# Pixel1_0_0.net
KiCad netlist of a schematic drawn in Altium Designer
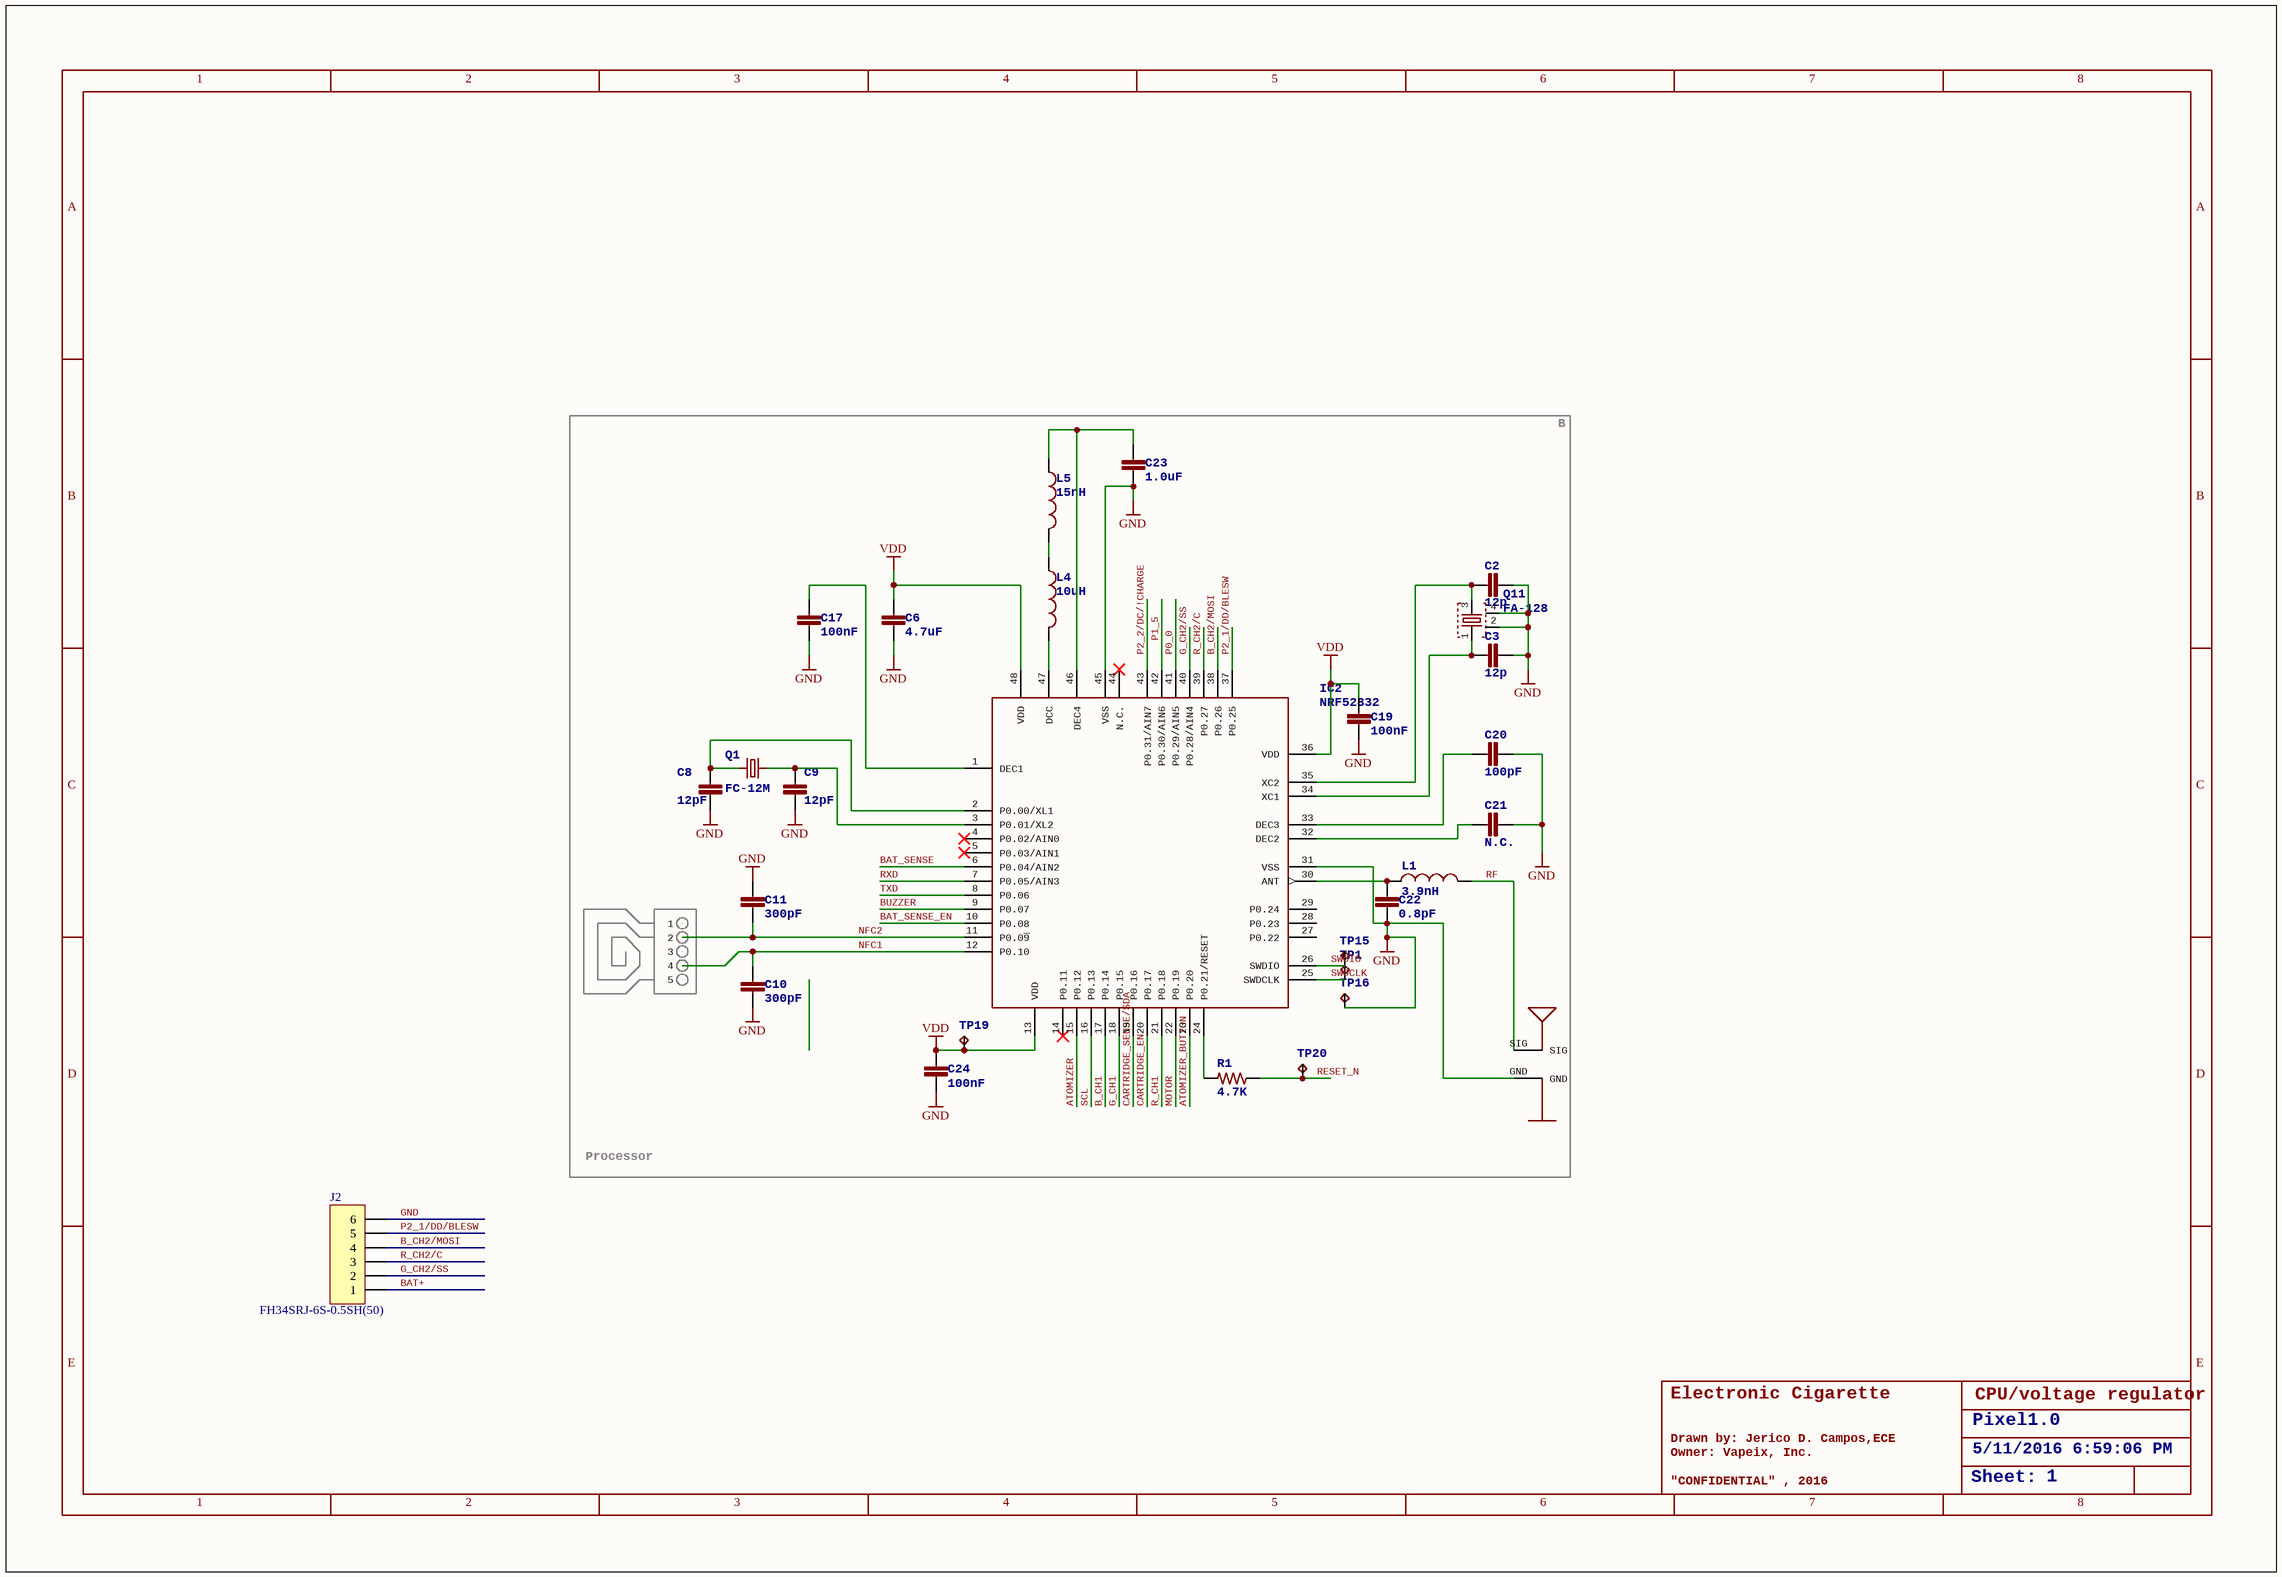
[diagram p0: Pixel1.0_0.SchDoc]

(export (version "E")
  (design (tool "Eeschema 10.0.6"))
  (components
    (comp (ref "ANT") (value "U.FL") (footprint "U.FL") (libsource (lib "Pixel1.0") (part "U.FL")))
    (comp (ref "C2")
      (value "12p")
      (footprint "C0201")
      (description "CAPACITOR, European symbol")
      (libsource (lib "") (part "C-EUC0201_1"))
    )
    (comp (ref "C3")
      (value "12p")
      (footprint "C0201")
      (description "CAPACITOR, European symbol")
      (libsource (lib "rcl") (part "C-EUC0201"))
    )
    (comp (ref "C6")
      (value "4.7uF")
      (footprint "C0201")
      (description "CAPACITOR, European symbol")
      (libsource (lib "") (part "C-EUC0201_2"))
    )
    (comp (ref "C8")
      (value "12pF")
      (footprint "C0201")
      (description "CAPACITOR, European symbol")
      (libsource (lib "") (part "C-EUC0201_2"))
    )
    (comp (ref "C9")
      (value "12pF")
      (footprint "C0201")
      (description "CAPACITOR, European symbol")
      (libsource (lib "") (part "C-EUC0201_2"))
    )
    (comp (ref "C10")
      (value "300pF")
      (footprint "C0201")
      (description "CAPACITOR, European symbol")
      (libsource (lib "") (part "C-EUC0201_2"))
    )
    (comp (ref "C11")
      (value "300pF")
      (footprint "C0201")
      (description "CAPACITOR, European symbol")
      (libsource (lib "") (part "C-EUC0201_3"))
    )
    (comp (ref "C17")
      (value "100nF")
      (footprint "C0201")
      (description "CAPACITOR, European symbol")
      (libsource (lib "") (part "C-EUC0201_2"))
    )
    (comp (ref "C19")
      (value "100nF")
      (footprint "C0201")
      (description "CAPACITOR, European symbol")
      (libsource (lib "") (part "C-EUC0201_2"))
    )
    (comp (ref "C20")
      (value "100pF")
      (footprint "C0201")
      (description "CAPACITOR, European symbol")
      (libsource (lib "rcl") (part "C-EUC0201"))
    )
    (comp (ref "C21")
      (value "N.C.")
      (footprint "C0201")
      (description "CAPACITOR, European symbol")
      (libsource (lib "rcl") (part "C-EUC0201"))
    )
    (comp (ref "C22")
      (value "0.8pF")
      (footprint "C0201")
      (description "CAPACITOR, European symbol")
      (libsource (lib "") (part "C-EUC0201_2"))
    )
    (comp (ref "C23")
      (value "1.0uF")
      (footprint "C0201")
      (description "CAPACITOR, European symbol")
      (libsource (lib "") (part "C-EUC0201_2"))
    )
    (comp (ref "C24")
      (value "100nF")
      (footprint "C0201")
      (description "CAPACITOR, European symbol")
      (libsource (lib "") (part "C-EUC0201_2"))
    )
    (comp (ref "IC2") (value "NRF52832") (footprint "QFN-48") (libsource (lib "FTDI") (part "NRF52832")))
    (comp (ref "J2")
      (value "FH34SRJ-6S-0.5SH(50)")
      (footprint "59453061110ECHLF")
      (description "WR-FPC 0.50mm SMT ZIF Horizontal Bottom Contact")
      (fields
        (field (name "MANUFACTURER") "Würth Elektronik eiSos GmbH")
        (field (name "PARTNO") "68710614522")
        (field (name "CREATED BY") "Karrer Zheng")
      )
      (libsource (lib "Components") (part "WE-ZIF Connector WR-FPC 68710614522"))
    )
    (comp (ref "L1") (value "3.9nH") (footprint "JE0402") (libsource (lib "vapeix") (part "LBEAD")))
    (comp (ref "L4") (value "10uH") (footprint "C0603") (libsource (lib "vapeix") (part "LBEAD")))
    (comp (ref "L5") (value "15nH") (footprint "JE0402") (libsource (lib "vapeix") (part "LBEAD")))
    (comp (ref "Q1")
      (value "FC-12M")
      (footprint "FC-12M")
      (description "kHz RANGE CRYSTAL UNIT   LOW PROFILE SMDSource: Epson Toyocom FC-12M.pdf")
      (libsource (lib "crystal") (part "FC-12M"))
    )
    (comp (ref "Q11")
      (value "FA-128")
      (footprint "FA-128")
      (description "MHz RANGE CRYSTAL UNIT    Source: Epson Toyocom")
      (libsource (lib "crystal") (part "FA-128"))
    )
    (comp (ref "R1")
      (value "4.7K")
      (footprint "R0201")
      (description "RESISTOR, American symbol")
      (libsource (lib "rcl") (part "R-US_R0201"))
    )
    (comp (ref "TP1")
      (value "TPTP06R")
      (footprint "TP06R")
      (description "Test pad")
      (libsource (lib "testpad") (part "TPTP06R"))
    )
    (comp (ref "TP15")
      (value "TPTP06R")
      (footprint "TP06R")
      (description "Test pad")
      (libsource (lib "testpad") (part "TPTP06R"))
    )
    (comp (ref "TP16")
      (value "TPTP06R")
      (footprint "TP06R")
      (description "Test pad")
      (libsource (lib "testpad") (part "TPTP06R"))
    )
    (comp (ref "TP19")
      (value "TPTP06R")
      (footprint "TP06R")
      (description "Test pad")
      (libsource (lib "testpad") (part "TPTP06R"))
    )
    (comp (ref "TP20")
      (value "TPTP06R")
      (footprint "TP06R")
      (description "Test pad")
      (libsource (lib "testpad") (part "TPTP06R"))
    )
    (comp (ref "U$2")
      (value "NFCCONNECTORMOLEX_5PIN")
      (footprint "NFC.CONN")
      (libsource (lib "vapeix") (part "NFCCONNECTORMOLEX_5PIN"))
    )
  )
  (nets
    (net (code "1") (name "/ATOMIZER") (class "Default")
      (node (ref "IC2") (pin "15") (pinfunction "P0.12_15") (pintype "passive"))
    )
    (net (code "2") (name "/ATOMIZER_BUTTON") (class "Default")
      (node (ref "IC2") (pin "23") (pinfunction "P0.20_23") (pintype "passive"))
    )
    (net (code "3") (name "/BAT+") (class "Default")
      (node (ref "J2") (pin "1") (pinfunction "1_1") (pintype "passive"))
    )
    (net (code "4") (name "/BAT_SENSE") (class "Default")
      (node (ref "IC2") (pin "6") (pinfunction "P0.04/AIN2_6") (pintype "passive"))
    )
    (net (code "5") (name "/BAT_SENSE_EN") (class "Default")
      (node (ref "IC2") (pin "10") (pinfunction "P0.08_10") (pintype "passive"))
    )
    (net (code "6") (name "/BUZZER") (class "Default")
      (node (ref "IC2") (pin "9") (pinfunction "P0.07_9") (pintype "passive"))
    )
    (net (code "7") (name "/B_CH1") (class "Default")
      (node (ref "IC2") (pin "17") (pinfunction "P0.14_17") (pintype "passive"))
    )
    (net (code "8") (name "/B_CH2{slash}MOSI") (class "Default")
      (node (ref "IC2") (pin "38") (pinfunction "P0.26_38") (pintype "passive"))
      (node (ref "J2") (pin "4") (pinfunction "4_4") (pintype "passive"))
    )
    (net (code "9") (name "/CARTRIDGE_EN") (class "Default")
      (node (ref "IC2") (pin "20") (pinfunction "P0.17_20") (pintype "passive"))
    )
    (net (code "10") (name "/CARTRIDGE_SENSE{slash}SDA") (class "Default")
      (node (ref "IC2") (pin "19") (pinfunction "P0.16_19") (pintype "passive"))
    )
    (net (code "11") (name "/G_CH1") (class "Default")
      (node (ref "IC2") (pin "18") (pinfunction "P0.15_18") (pintype "passive"))
    )
    (net (code "12") (name "/G_CH2{slash}SS") (class "Default")
      (node (ref "IC2") (pin "40") (pinfunction "P0.28/AIN4_40") (pintype "passive"))
      (node (ref "J2") (pin "2") (pinfunction "2_2") (pintype "passive"))
    )
    (net (code "13") (name "/MOTOR") (class "Default")
      (node (ref "IC2") (pin "22") (pinfunction "P0.19_22") (pintype "passive"))
    )
    (net (code "14") (name "/NFC1") (class "Default")
      (node (ref "C10") (pin "1") (pinfunction "1_1") (pintype "passive"))
      (node (ref "IC2") (pin "12") (pinfunction "P0.10_12") (pintype "passive"))
      (node (ref "U$2") (pin "4") (pinfunction "4_4") (pintype "passive"))
    )
    (net (code "15") (name "/NFC2") (class "Default")
      (node (ref "C11") (pin "1") (pinfunction "1_1") (pintype "passive"))
      (node (ref "IC2") (pin "11") (pinfunction "P0.0~{9}_11") (pintype "passive"))
      (node (ref "U$2") (pin "2") (pinfunction "2_2") (pintype "passive"))
    )
    (net (code "16") (name "/P0_0") (class "Default")
      (node (ref "IC2") (pin "41") (pinfunction "P0.29/AIN5_41") (pintype "passive"))
    )
    (net (code "17") (name "/P1_5") (class "Default")
      (node (ref "IC2") (pin "42") (pinfunction "P0.30/AIN6_42") (pintype "passive"))
    )
    (net (code "18") (name "/P2_1{slash}DD{slash}BLESW") (class "Default")
      (node (ref "IC2") (pin "37") (pinfunction "P0.25_37") (pintype "passive"))
      (node (ref "J2") (pin "5") (pinfunction "5_5") (pintype "passive"))
    )
    (net (code "19") (name "/P2_2{slash}DC{slash}!CHARGE") (class "Default")
      (node (ref "IC2") (pin "43") (pinfunction "P0.31/AIN7_43") (pintype "passive"))
    )
    (net (code "20") (name "/RESET_N") (class "Default")
      (node (ref "R1") (pin "1") (pinfunction "1_1") (pintype "passive"))
      (node (ref "TP20") (pin "TP") (pinfunction "TP_TP") (pintype "passive"))
    )
    (net (code "21") (name "/RF") (class "Default")
      (node (ref "ANT") (pin "SIG") (pinfunction "SIG_SIG") (pintype "passive"))
      (node (ref "L1") (pin "2") (pinfunction "2_2") (pintype "passive"))
    )
    (net (code "22") (name "/RXD") (class "Default")
      (node (ref "IC2") (pin "7") (pinfunction "P0.05/AIN3_7") (pintype "passive"))
    )
    (net (code "23") (name "/R_CH1") (class "Default")
      (node (ref "IC2") (pin "21") (pinfunction "P0.18_21") (pintype "passive"))
    )
    (net (code "24") (name "/R_CH2{slash}C") (class "Default")
      (node (ref "IC2") (pin "39") (pinfunction "P0.27_39") (pintype "passive"))
      (node (ref "J2") (pin "3") (pinfunction "3_3") (pintype "passive"))
    )
    (net (code "25") (name "/SCL") (class "Default")
      (node (ref "IC2") (pin "16") (pinfunction "P0.13_16") (pintype "passive"))
    )
    (net (code "26") (name "/SWDCLK") (class "Default")
      (node (ref "IC2") (pin "25") (pinfunction "SWDCLK_25") (pintype "open_collector"))
      (node (ref "TP1") (pin "TP") (pinfunction "TP_TP") (pintype "passive"))
    )
    (net (code "27") (name "/SWDIO") (class "Default")
      (node (ref "IC2") (pin "26") (pinfunction "SWDIO_26") (pintype "open_collector"))
      (node (ref "TP15") (pin "TP") (pinfunction "TP_TP") (pintype "passive"))
    )
    (net (code "28") (name "/TXD") (class "Default")
      (node (ref "IC2") (pin "8") (pinfunction "P0.06_8") (pintype "passive"))
    )
    (net (code "29") (name "GND") (class "Default")
      (node (ref "ANT") (pin "GND") (pinfunction "GND_GND") (pintype "passive"))
      (node (ref "C10") (pin "2") (pinfunction "2_2") (pintype "passive"))
      (node (ref "C11") (pin "2") (pinfunction "2_2") (pintype "passive"))
      (node (ref "C17") (pin "2") (pinfunction "2_2") (pintype "passive"))
      (node (ref "C19") (pin "2") (pinfunction "2_2") (pintype "passive"))
      (node (ref "C2") (pin "2") (pinfunction "2_2") (pintype "passive"))
      (node (ref "C20") (pin "1") (pinfunction "1_1") (pintype "passive"))
      (node (ref "C21") (pin "1") (pinfunction "1_1") (pintype "passive"))
      (node (ref "C22") (pin "2") (pinfunction "2_2") (pintype "passive"))
      (node (ref "C23") (pin "2") (pinfunction "2_2") (pintype "passive"))
      (node (ref "C24") (pin "2") (pinfunction "2_2") (pintype "passive"))
      (node (ref "C3") (pin "1") (pinfunction "1_1") (pintype "passive"))
      (node (ref "C6") (pin "2") (pinfunction "2_2") (pintype "passive"))
      (node (ref "C8") (pin "2") (pinfunction "2_2") (pintype "passive"))
      (node (ref "C9") (pin "2") (pinfunction "2_2") (pintype "passive"))
      (node (ref "IC2") (pin "31") (pinfunction "VSS_31") (pintype "power_in"))
      (node (ref "IC2") (pin "45") (pinfunction "VSS_45") (pintype "power_in"))
      (node (ref "J2") (pin "6") (pinfunction "6_6") (pintype "passive"))
      (node (ref "Q11") (pin "2") (pinfunction "2_2") (pintype "passive"))
      (node (ref "Q11") (pin "4") (pinfunction "4_4") (pintype "passive"))
      (node (ref "TP16") (pin "TP") (pinfunction "TP_TP") (pintype "passive"))
    )
    (net (code "30") (name "Net-(IC2-ANT)") (class "Default")
      (node (ref "C22") (pin "1") (pinfunction "1_1") (pintype "passive"))
      (node (ref "IC2") (pin "30") (pinfunction "ANT_30") (pintype "output"))
      (node (ref "L1") (pin "1") (pinfunction "1_1") (pintype "passive"))
    )
    (net (code "31") (name "Net-(IC2-DCC)") (class "Default")
      (node (ref "IC2") (pin "47") (pinfunction "DCC_47") (pintype "power_in"))
      (node (ref "L4") (pin "2") (pinfunction "2_2") (pintype "passive"))
    )
    (net (code "32") (name "Net-(IC2-DEC1)") (class "Default")
      (node (ref "C17") (pin "1") (pinfunction "1_1") (pintype "passive"))
      (node (ref "IC2") (pin "1") (pinfunction "DEC1_1") (pintype "power_in"))
    )
    (net (code "33") (name "Net-(IC2-DEC2)") (class "Default")
      (node (ref "C21") (pin "2") (pinfunction "2_2") (pintype "passive"))
      (node (ref "IC2") (pin "32") (pinfunction "DEC2_32") (pintype "power_in"))
    )
    (net (code "34") (name "Net-(IC2-DEC3)") (class "Default")
      (node (ref "C20") (pin "2") (pinfunction "2_2") (pintype "passive"))
      (node (ref "IC2") (pin "33") (pinfunction "DEC3_33") (pintype "power_in"))
    )
    (net (code "35") (name "Net-(IC2-DEC4)") (class "Default")
      (node (ref "C23") (pin "1") (pinfunction "1_1") (pintype "passive"))
      (node (ref "IC2") (pin "46") (pinfunction "DEC4_46") (pintype "power_in"))
      (node (ref "L5") (pin "1") (pinfunction "1_1") (pintype "passive"))
    )
    (net (code "36") (name "Net-(IC2-P0.00{slash}XL1)") (class "Default")
      (node (ref "C8") (pin "1") (pinfunction "1_1") (pintype "passive"))
      (node (ref "IC2") (pin "2") (pinfunction "P0.00/XL1_2") (pintype "passive"))
      (node (ref "Q1") (pin "1") (pinfunction "1_1") (pintype "passive"))
    )
    (net (code "37") (name "Net-(IC2-P0.01{slash}XL2)") (class "Default")
      (node (ref "C9") (pin "1") (pinfunction "1_1") (pintype "passive"))
      (node (ref "IC2") (pin "3") (pinfunction "P0.01/XL2_3") (pintype "passive"))
      (node (ref "Q1") (pin "2") (pinfunction "2_2") (pintype "passive"))
    )
    (net (code "38") (name "Net-(IC2-P0.21{slash}RESET)") (class "Default")
      (node (ref "IC2") (pin "24") (pinfunction "P0.21/RESET_24") (pintype "passive"))
      (node (ref "R1") (pin "2") (pinfunction "2_2") (pintype "passive"))
    )
    (net (code "39") (name "Net-(IC2-XC1)") (class "Default")
      (node (ref "C3") (pin "2") (pinfunction "2_2") (pintype "passive"))
      (node (ref "IC2") (pin "34") (pinfunction "XC1_34") (pintype "open_collector"))
      (node (ref "Q11") (pin "1") (pinfunction "1_1") (pintype "passive"))
    )
    (net (code "40") (name "Net-(IC2-XC2)") (class "Default")
      (node (ref "C2") (pin "1") (pinfunction "1_1") (pintype "passive"))
      (node (ref "IC2") (pin "35") (pinfunction "XC2_35") (pintype "open_collector"))
      (node (ref "Q11") (pin "3") (pinfunction "3_3") (pintype "passive"))
    )
    (net (code "41") (name "Net-(L4-Pad1)") (class "Default")
      (node (ref "L4") (pin "1") (pinfunction "1_1") (pintype "passive"))
      (node (ref "L5") (pin "2") (pinfunction "2_2") (pintype "passive"))
    )
    (net (code "42") (name "VDD") (class "Default")
      (node (ref "C19") (pin "1") (pinfunction "1_1") (pintype "passive"))
      (node (ref "C24") (pin "1") (pinfunction "1_1") (pintype "passive"))
      (node (ref "C6") (pin "1") (pinfunction "1_1") (pintype "passive"))
      (node (ref "IC2") (pin "13") (pinfunction "VDD_13") (pintype "passive"))
      (node (ref "IC2") (pin "36") (pinfunction "VDD_36") (pintype "power_in"))
      (node (ref "IC2") (pin "48") (pinfunction "VDD_48") (pintype "power_in"))
      (node (ref "TP19") (pin "TP") (pinfunction "TP_TP") (pintype "passive"))
    )
    (net (code "43") (name "unconnected-(IC2-N.C.-Pad44)") (class "Default")
      (node (ref "IC2") (pin "44") (pinfunction "N.C._44") (pintype "passive+no_connect"))
    )
    (net (code "44") (name "unconnected-(IC2-P0.02{slash}AIN0-Pad4)") (class "Default")
      (node (ref "IC2") (pin "4") (pinfunction "P0.02/AIN0_4") (pintype "passive+no_connect"))
    )
    (net (code "45") (name "unconnected-(IC2-P0.03{slash}AIN1-Pad5)") (class "Default")
      (node (ref "IC2") (pin "5") (pinfunction "P0.03/AIN1_5") (pintype "passive+no_connect"))
    )
    (net (code "46") (name "unconnected-(IC2-P0.11-Pad14)") (class "Default")
      (node (ref "IC2") (pin "14") (pinfunction "P0.11_14") (pintype "passive+no_connect"))
    )
    (net (code "47") (name "unconnected-(IC2-P0.22-Pad27)") (class "Default")
      (node (ref "IC2") (pin "27") (pinfunction "P0.22_27") (pintype "passive"))
    )
    (net (code "48") (name "unconnected-(IC2-P0.23-Pad28)") (class "Default")
      (node (ref "IC2") (pin "28") (pinfunction "P0.23_28") (pintype "passive"))
    )
    (net (code "49") (name "unconnected-(IC2-P0.24-Pad29)") (class "Default")
      (node (ref "IC2") (pin "29") (pinfunction "P0.24_29") (pintype "passive"))
    )
    (net (code "50") (name "unconnected-(U$2-Pad1)") (class "Default")
      (node (ref "U$2") (pin "1") (pinfunction "1_1") (pintype "passive"))
    )
    (net (code "51") (name "unconnected-(U$2-Pad3)") (class "Default")
      (node (ref "U$2") (pin "3") (pinfunction "3_3") (pintype "passive"))
    )
    (net (code "52") (name "unconnected-(U$2-Pad5)") (class "Default")
      (node (ref "U$2") (pin "5") (pinfunction "5_5") (pintype "passive"))
    )
  )
)
